# adc_lemon.net
KiCad netlist of a schematic drawn in EAGLE
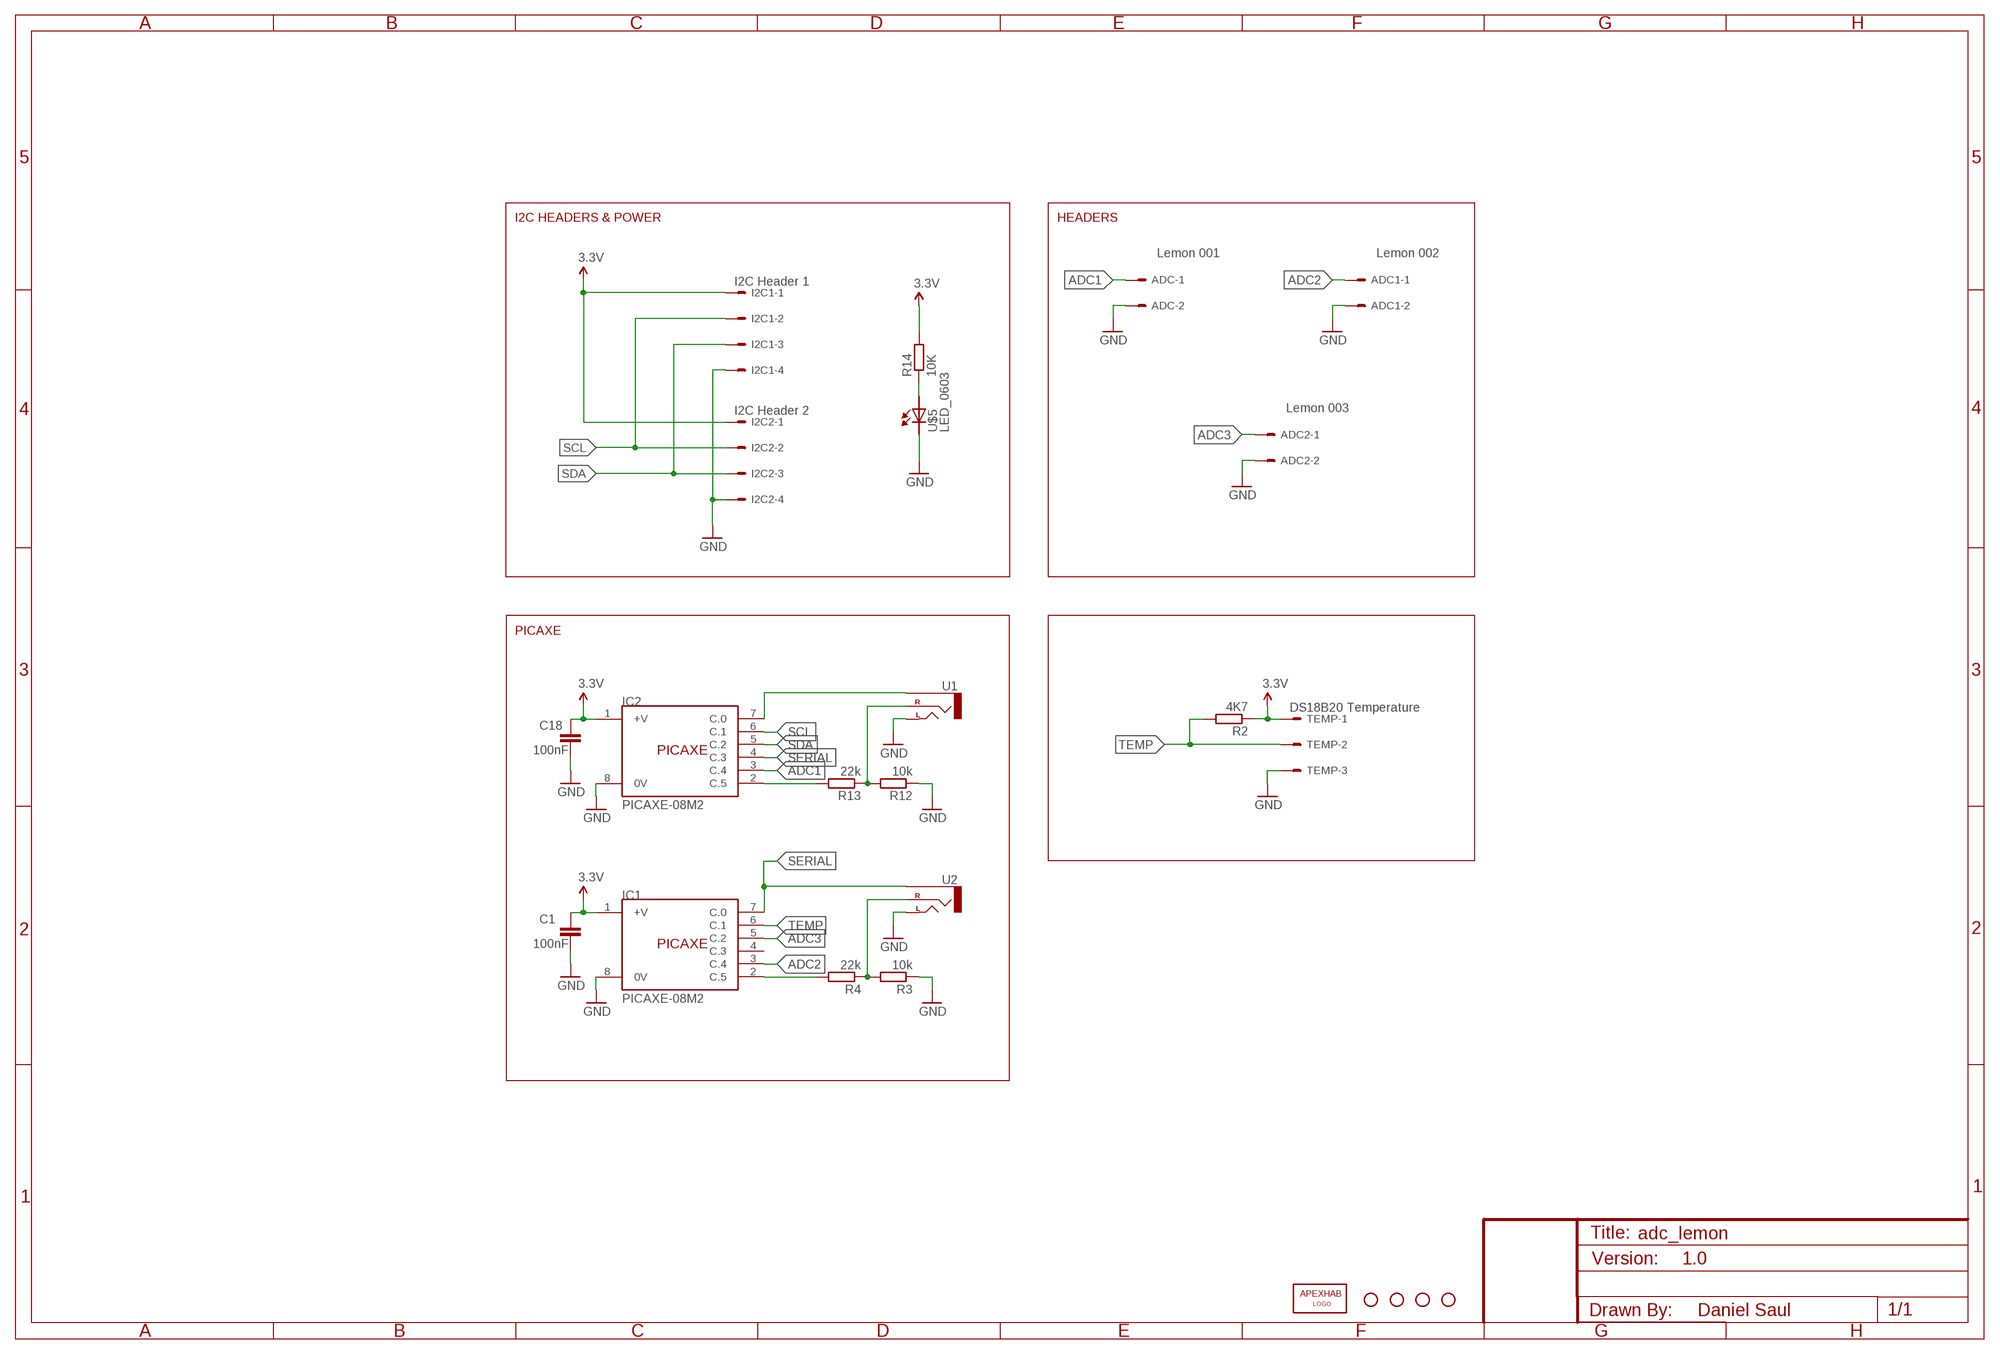
[diagram p0: schematic, sheet 1]

(export (version "E")
  (design (tool "Eeschema 10.0.6"))
  (components
    (comp (ref "ADC")
      (value "Lemon 001")
      (footprint "eagle-import:6410-02")
      (libsource (lib "eagle-import") (part "22-?-0227-2021"))
    )
    (comp (ref "ADC1")
      (value "Lemon 002")
      (footprint "eagle-import:6410-02")
      (libsource (lib "eagle-import") (part "22-?-0227-2021"))
    )
    (comp (ref "ADC2")
      (value "Lemon 003")
      (footprint "eagle-import:6410-02")
      (libsource (lib "eagle-import") (part "22-?-0227-2021"))
    )
    (comp (ref "C1")
      (value "100nF")
      (footprint "eagle-import:C0805")
      (libsource (lib "eagle-import") (part "C-EUC0805"))
    )
    (comp (ref "C18")
      (value "100nF")
      (footprint "eagle-import:C0805")
      (libsource (lib "eagle-import") (part "C-EUC0805"))
    )
    (comp (ref "I2C1")
      (value "I2C Header 1")
      (footprint "eagle-import:6410-04")
      (libsource (lib "eagle-import") (part "22-?-0427-2041"))
    )
    (comp (ref "I2C2")
      (value "I2C Header 2")
      (footprint "eagle-import:6410-04")
      (libsource (lib "eagle-import") (part "22-?-0427-2041"))
    )
    (comp (ref "IC1")
      (value "PICAXE-08M2")
      (footprint "eagle-import:SOIC8")
      (libsource (lib "eagle-import") (part "PICAXE-08M2"))
    )
    (comp (ref "IC2")
      (value "PICAXE-08M2")
      (footprint "eagle-import:SOIC8")
      (libsource (lib "eagle-import") (part "PICAXE-08M2"))
    )
    (comp (ref "JP1")
      (value "APEXHAB-LOGO_APEXHAB-SMALL")
      (footprint "eagle-import:APEXHAB-LOGO-SMALL")
      (libsource (lib "eagle-import") (part "APEXHAB-LOGO_APEXHAB-SMALL"))
    )
    (comp (ref "JP2")
      (value "STAND-OFF")
      (footprint "eagle-import:STAND-OFF")
      (libsource (lib "eagle-import") (part "STAND-OFF"))
    )
    (comp (ref "JP3")
      (value "STAND-OFF")
      (footprint "eagle-import:STAND-OFF")
      (libsource (lib "eagle-import") (part "STAND-OFF"))
    )
    (comp (ref "JP4")
      (value "STAND-OFF")
      (footprint "eagle-import:STAND-OFF")
      (libsource (lib "eagle-import") (part "STAND-OFF"))
    )
    (comp (ref "JP5")
      (value "STAND-OFF")
      (footprint "eagle-import:STAND-OFF")
      (libsource (lib "eagle-import") (part "STAND-OFF"))
    )
    (comp (ref "R2")
      (value "4K7")
      (footprint "eagle-import:R0805")
      (libsource (lib "eagle-import") (part "R-EU_R0805"))
    )
    (comp (ref "R3")
      (value "10k")
      (footprint "eagle-import:R0805")
      (libsource (lib "eagle-import") (part "R-EU_R0805"))
    )
    (comp (ref "R4")
      (value "22k")
      (footprint "eagle-import:R0805")
      (libsource (lib "eagle-import") (part "R-EU_R0805"))
    )
    (comp (ref "R12")
      (value "10k")
      (footprint "eagle-import:R0805")
      (libsource (lib "eagle-import") (part "R-EU_R0805"))
    )
    (comp (ref "R13")
      (value "22k")
      (footprint "eagle-import:R0805")
      (libsource (lib "eagle-import") (part "R-EU_R0805"))
    )
    (comp (ref "R14")
      (value "10K")
      (footprint "eagle-import:R0805")
      (libsource (lib "eagle-import") (part "R-EU_R0805"))
    )
    (comp (ref "TEMP")
      (value "DS18B20 Temperature")
      (footprint "eagle-import:6410-03")
      (libsource (lib "eagle-import") (part "22-?-0327-2031"))
    )
    (comp (ref "U$5")
      (value "LED_0603")
      (footprint "eagle-import:CHIPLED_0603")
      (libsource (lib "eagle-import") (part "LED_0603"))
    )
    (comp (ref "U1")
      (value "AUDIO-JACKPTH")
      (footprint "eagle-import:AUDIO-JACK")
      (libsource (lib "eagle-import") (part "AUDIO-JACKPTH"))
    )
    (comp (ref "U2")
      (value "AUDIO-JACKPTH")
      (footprint "eagle-import:AUDIO-JACK")
      (libsource (lib "eagle-import") (part "AUDIO-JACKPTH"))
    )
  )
  (nets
    (net (code "1") (name "3.3V") (class "Default")
      (node (ref "C1") (pin "1") (pinfunction "1_1") (pintype "passive"))
      (node (ref "C18") (pin "1") (pinfunction "1_1") (pintype "passive"))
      (node (ref "I2C1") (pin "1") (pinfunction "S_1") (pintype "passive"))
      (node (ref "I2C2") (pin "1") (pinfunction "S_1") (pintype "passive"))
      (node (ref "IC1") (pin "1") (pinfunction "+V_1") (pintype "power_in"))
      (node (ref "IC2") (pin "1") (pinfunction "+V_1") (pintype "power_in"))
      (node (ref "R14") (pin "2") (pinfunction "2_2") (pintype "passive"))
      (node (ref "R2") (pin "1") (pinfunction "1_1") (pintype "passive"))
      (node (ref "TEMP") (pin "1") (pinfunction "S_1") (pintype "passive"))
    )
    (net (code "2") (name "ADC1") (class "Default")
      (node (ref "ADC") (pin "1") (pinfunction "S_1") (pintype "passive"))
      (node (ref "IC2") (pin "3") (pinfunction "C.4_3") (pintype "bidirectional"))
    )
    (net (code "3") (name "ADC2") (class "Default")
      (node (ref "ADC1") (pin "1") (pinfunction "S_1") (pintype "passive"))
      (node (ref "IC1") (pin "3") (pinfunction "C.4_3") (pintype "bidirectional"))
    )
    (net (code "4") (name "ADC3") (class "Default")
      (node (ref "ADC2") (pin "1") (pinfunction "S_1") (pintype "passive"))
      (node (ref "IC1") (pin "5") (pinfunction "C.2_5") (pintype "bidirectional"))
    )
    (net (code "5") (name "GND") (class "Default")
      (node (ref "ADC") (pin "2") (pinfunction "S_2") (pintype "passive"))
      (node (ref "ADC1") (pin "2") (pinfunction "S_2") (pintype "passive"))
      (node (ref "ADC2") (pin "2") (pinfunction "S_2") (pintype "passive"))
      (node (ref "C1") (pin "2") (pinfunction "2_2") (pintype "passive"))
      (node (ref "C18") (pin "2") (pinfunction "2_2") (pintype "passive"))
      (node (ref "I2C1") (pin "4") (pinfunction "S_4") (pintype "passive"))
      (node (ref "I2C2") (pin "4") (pinfunction "S_4") (pintype "passive"))
      (node (ref "IC1") (pin "8") (pinfunction "0V_8") (pintype "power_in"))
      (node (ref "IC2") (pin "8") (pinfunction "0V_8") (pintype "power_in"))
      (node (ref "R12") (pin "1") (pinfunction "1_1") (pintype "passive"))
      (node (ref "R3") (pin "1") (pinfunction "1_1") (pintype "passive"))
      (node (ref "TEMP") (pin "3") (pinfunction "S_3") (pintype "passive"))
      (node (ref "U$5") (pin "C") (pinfunction "C_C") (pintype "passive"))
      (node (ref "U1") (pin "TIP") (pinfunction "LEFT_TIP") (pintype "bidirectional"))
      (node (ref "U2") (pin "TIP") (pinfunction "LEFT_TIP") (pintype "bidirectional"))
    )
    (net (code "6") (name "Net-(IC1-C.5)") (class "Default")
      (node (ref "IC1") (pin "2") (pinfunction "C.5_2") (pintype "bidirectional"))
      (node (ref "R4") (pin "2") (pinfunction "2_2") (pintype "passive"))
    )
    (net (code "7") (name "Net-(IC2-C.0)") (class "Default")
      (node (ref "IC2") (pin "7") (pinfunction "C.0_7") (pintype "bidirectional"))
      (node (ref "U1") (pin "SLEEVE") (pinfunction "SLEEVE_SLEEVE") (pintype "bidirectional"))
    )
    (net (code "8") (name "Net-(IC2-C.5)") (class "Default")
      (node (ref "IC2") (pin "2") (pinfunction "C.5_2") (pintype "bidirectional"))
      (node (ref "R13") (pin "2") (pinfunction "2_2") (pintype "passive"))
    )
    (net (code "9") (name "Net-(R14-Pad1)") (class "Default")
      (node (ref "R14") (pin "1") (pinfunction "1_1") (pintype "passive"))
      (node (ref "U$5") (pin "A") (pinfunction "A_A") (pintype "passive"))
    )
    (net (code "10") (name "Net-(U1-RIGHT)") (class "Default")
      (node (ref "R12") (pin "2") (pinfunction "2_2") (pintype "passive"))
      (node (ref "R13") (pin "1") (pinfunction "1_1") (pintype "passive"))
      (node (ref "U1") (pin "RING") (pinfunction "RIGHT_RING") (pintype "bidirectional"))
    )
    (net (code "11") (name "Net-(U2-RIGHT)") (class "Default")
      (node (ref "R3") (pin "2") (pinfunction "2_2") (pintype "passive"))
      (node (ref "R4") (pin "1") (pinfunction "1_1") (pintype "passive"))
      (node (ref "U2") (pin "RING") (pinfunction "RIGHT_RING") (pintype "bidirectional"))
    )
    (net (code "12") (name "SCL") (class "Default")
      (node (ref "I2C1") (pin "2") (pinfunction "S_2") (pintype "passive"))
      (node (ref "I2C2") (pin "2") (pinfunction "S_2") (pintype "passive"))
      (node (ref "IC2") (pin "6") (pinfunction "C.1_6") (pintype "bidirectional"))
    )
    (net (code "13") (name "SDA") (class "Default")
      (node (ref "I2C1") (pin "3") (pinfunction "S_3") (pintype "passive"))
      (node (ref "I2C2") (pin "3") (pinfunction "S_3") (pintype "passive"))
      (node (ref "IC2") (pin "5") (pinfunction "C.2_5") (pintype "bidirectional"))
    )
    (net (code "14") (name "SERIAL") (class "Default")
      (node (ref "IC1") (pin "7") (pinfunction "C.0_7") (pintype "bidirectional"))
      (node (ref "IC2") (pin "4") (pinfunction "C.3_4") (pintype "bidirectional"))
      (node (ref "U2") (pin "SLEEVE") (pinfunction "SLEEVE_SLEEVE") (pintype "bidirectional"))
    )
    (net (code "15") (name "TEMP") (class "Default")
      (node (ref "IC1") (pin "6") (pinfunction "C.1_6") (pintype "bidirectional"))
      (node (ref "R2") (pin "2") (pinfunction "2_2") (pintype "passive"))
      (node (ref "TEMP") (pin "2") (pinfunction "S_2") (pintype "passive"))
    )
    (net (code "16") (name "unconnected-(IC1-C.3-Pad4)") (class "Default")
      (node (ref "IC1") (pin "4") (pinfunction "C.3_4") (pintype "bidirectional"))
    )
  )
)
